# Connectors.net
KiCad netlist of a schematic drawn in Altium Designer
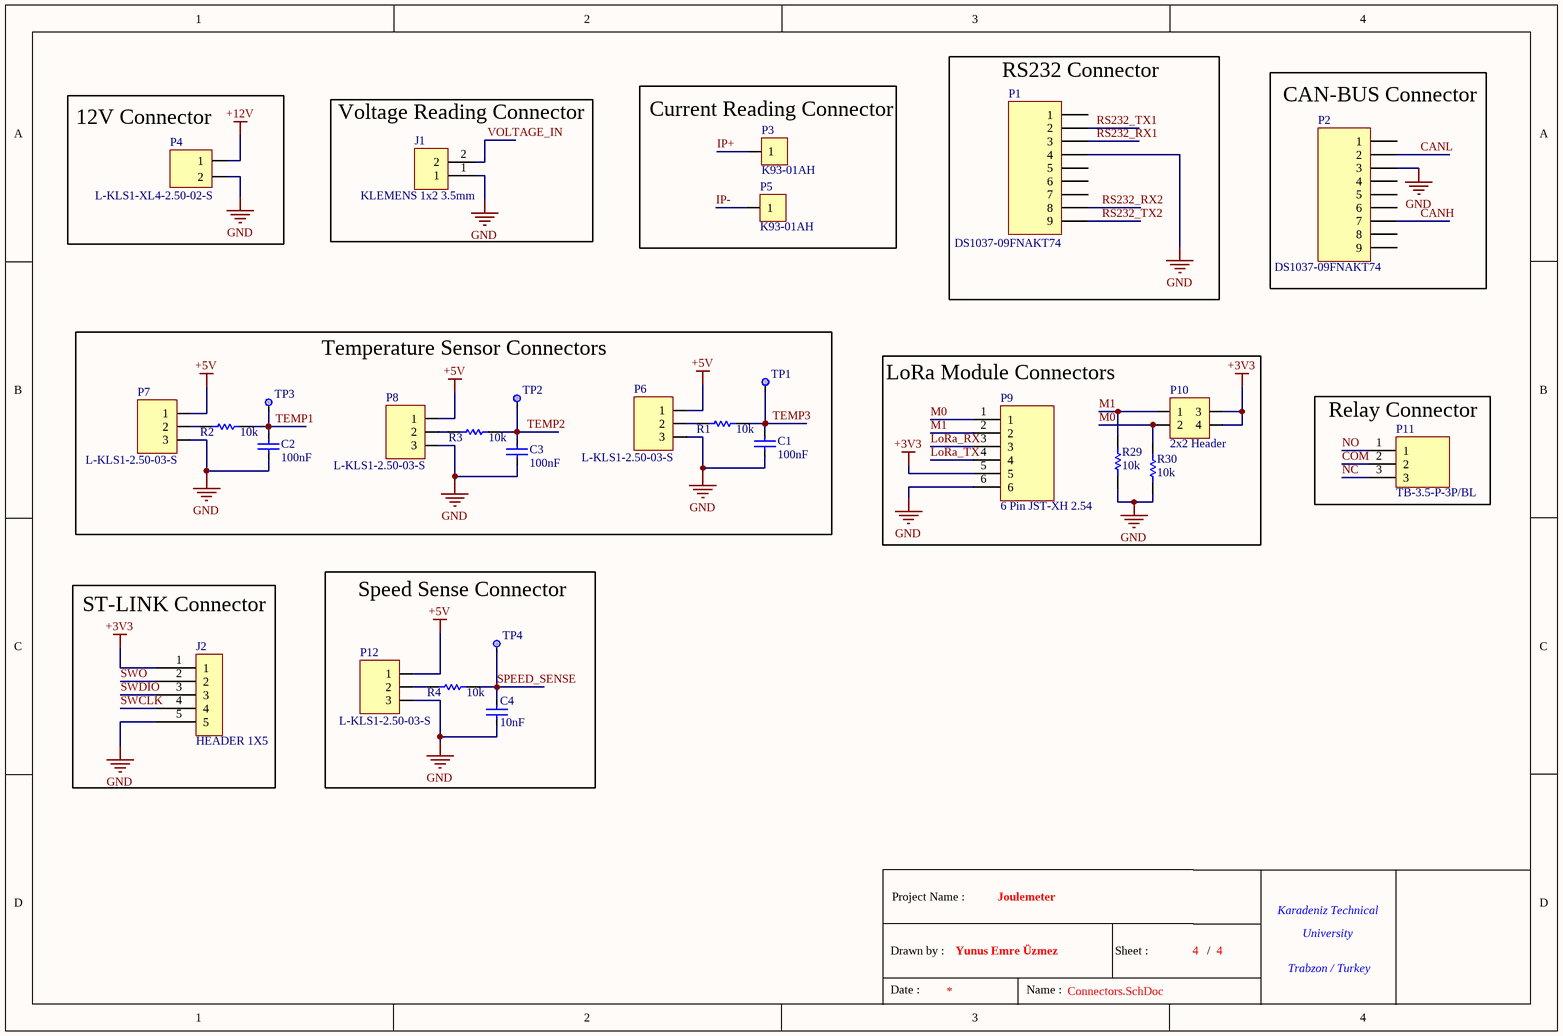
[diagram p0: Connectors.SchDoc]

(export (version "E")
  (design (tool "Eeschema 10.0.6"))
  (components
    (comp (ref "C1")
      (value "100nF")
      (footprint "CAP-0603")
      (fields
        (field (name "MANUFACTURER") "TDK")
        (field (name "VOLTAGE") "50V")
        (field (name "TOLERANCE") "%10")
      )
      (libsource (lib "My_Libs") (part "CGA3E2X7R1H104K080AA"))
    )
    (comp (ref "C2")
      (value "100nF")
      (footprint "Motor_Driver:CAP-0603")
      (fields
        (field (name "MANUFACTURER") "TDK")
        (field (name "VOLTAGE") "50V")
        (field (name "TOLERANCE") "%10")
      )
      (libsource (lib "My_Libs") (part "CGA3E2X7R1H104K080AA"))
    )
    (comp (ref "C3")
      (value "100nF")
      (footprint "Motor_Driver:CAP-0603")
      (fields
        (field (name "MANUFACTURER") "TDK")
        (field (name "VOLTAGE") "50V")
        (field (name "TOLERANCE") "%10")
      )
      (libsource (lib "My_Libs") (part "CGA3E2X7R1H104K080AA"))
    )
    (comp (ref "C4")
      (value "10nF")
      (footprint "CAP-0603")
      (fields
        (field (name "MANUFACTURER") "AVX")
        (field (name "VOLTAGE") "100V")
        (field (name "TOLERANCE") "%10")
      )
      (libsource (lib "Capacitor") (part "06031C103K4T4A"))
    )
    (comp (ref "J1")
      (value "KLEMENS 1x2 3.5mm")
      (footprint "Klemens 1X2 3.5mm")
      (description "1x2 3.5mm Klemens")
      (libsource (lib "model_satellite") (part "KLEMENS 1x2 3.5mm"))
    )
    (comp (ref "J2")
      (value "HEADER 1X5")
      (footprint "Header 2.54 1x5")
      (description "2.54mm 1x5 Header")
      (libsource (lib "model_satellite") (part "HEADER 1X5"))
    )
    (comp (ref "P1")
      (value "DS1037-09FNAKT74")
      (footprint "D SUB 9PIN FEMALE 90C TH")
      (fields (field (name "MANUFACTURER") "CONNFLY"))
      (libsource (lib "Motor_Driver") (part "DS1037-09FNAKT74"))
    )
    (comp (ref "P2")
      (value "DS1037-09FNAKT74")
      (footprint "D SUB 9PIN FEMALE 90C TH")
      (fields (field (name "MANUFACTURER") "CONNFLY"))
      (libsource (lib "Motor_Driver") (part "DS1037-09FNAKT74"))
    )
    (comp (ref "P3")
      (value "K93-01AH")
      (footprint "TERM.BLK.5.00MM BARRIER TYPE")
      (fields (field (name "MANUFACTURER") "GAOSONG"))
      (libsource (lib "Motor_Driver") (part "K93-01AH"))
    )
    (comp (ref "P4")
      (value "L-KLS1-XL4-2.50-02-S")
      (footprint "Motor_Driver_Module:2 PIN MALE 180C TH 2.50MM")
      (fields (field (name "MANUFACTURER") "KLS ELECTRONIC"))
      (libsource (lib "Motor_Driver_Module") (part "L-KLS1-XL4-2.50-02-S"))
    )
    (comp (ref "P5")
      (value "K93-01AH")
      (footprint "TERM.BLK.5.00MM BARRIER TYPE")
      (fields (field (name "MANUFACTURER") "GAOSONG"))
      (libsource (lib "Motor_Driver") (part "K93-01AH"))
    )
    (comp (ref "P6")
      (value "L-KLS1-2.50-03-S")
      (footprint "Motor_Driver:3PIN MALE 180C TH 2.5mm")
      (fields (field (name "MANUFACTURER") "KLS ELECTRONIC"))
      (libsource (lib "Motor_Driver_Module") (part "L-KLS1-2.50-03-S"))
    )
    (comp (ref "P7")
      (value "L-KLS1-2.50-03-S")
      (footprint "Motor_Driver:3PIN MALE 180C TH 2.5mm")
      (fields (field (name "MANUFACTURER") "KLS ELECTRONIC"))
      (libsource (lib "Motor_Driver_Module") (part "L-KLS1-2.50-03-S"))
    )
    (comp (ref "P8")
      (value "L-KLS1-2.50-03-S")
      (footprint "Motor_Driver:3PIN MALE 180C TH 2.5mm")
      (fields (field (name "MANUFACTURER") "KLS ELECTRONIC"))
      (libsource (lib "Motor_Driver_Module") (part "L-KLS1-2.50-03-S"))
    )
    (comp (ref "P9")
      (value "6 Pin JST-XH 2.54")
      (footprint "jl_lib:1x6 2.50mm TUNIC CONNECTOR")
      (fields (field (name "MANUFACTURER") "CONNFLY"))
      (libsource (lib "jl_lib") (part "6 Pin JST-XH 2.54"))
    )
    (comp (ref "P10")
      (value "2x2 Header")
      (footprint "2x2 Header (2.54mm)")
      (libsource (lib "Motor_Driver") (part "2x2 Header (2.54mm)"))
    )
    (comp (ref "P11")
      (value "TB-3.5-P-3P/BL")
      (footprint "1x3 3.50MM TERMINAL BLOCK")
      (fields (field (name "MANUFACTURER") "NINIGI"))
      (libsource (lib "jl_lib") (part "TB-3.5-P-3P/BL"))
    )
    (comp (ref "P12")
      (value "L-KLS1-2.50-03-S")
      (footprint "Motor_Driver:3PIN MALE 180C TH 2.5mm")
      (fields (field (name "MANUFACTURER") "KLS ELECTRONIC"))
      (libsource (lib "Motor_Driver_Module") (part "L-KLS1-2.50-03-S"))
    )
    (comp (ref "R1")
      (value "10k")
      (footprint "Motor_Driver:RES-0603")
      (fields
        (field (name "MANUFACTURER") "Vishay")
        (field (name "TOLERANCE") "%1")
        (field (name "POWER") "0.1W")
      )
      (libsource (lib "My_Libs") (part "CRCW060310K0FKEA"))
    )
    (comp (ref "R2")
      (value "10k")
      (footprint "Motor_Driver:RES-0603")
      (fields
        (field (name "MANUFACTURER") "Vishay")
        (field (name "TOLERANCE") "%1")
        (field (name "POWER") "0.1W")
      )
      (libsource (lib "My_Libs") (part "CRCW060310K0FKEA"))
    )
    (comp (ref "R3")
      (value "10k")
      (footprint "Motor_Driver:RES-0603")
      (fields
        (field (name "MANUFACTURER") "Vishay")
        (field (name "TOLERANCE") "%1")
        (field (name "POWER") "0.1W")
      )
      (libsource (lib "My_Libs") (part "CRCW060310K0FKEA"))
    )
    (comp (ref "R4")
      (value "10k")
      (footprint "Motor_Driver:RES-0603")
      (fields
        (field (name "MANUFACTURER") "Vishay")
        (field (name "TOLERANCE") "%1")
        (field (name "POWER") "0.1W")
      )
      (libsource (lib "My_Libs") (part "CRCW060310K0FKEA"))
    )
    (comp (ref "R29")
      (value "10k")
      (footprint "RES-0603")
      (fields
        (field (name "MANUFACTURER") "Vishay")
        (field (name "TOLERANCE") "%1")
        (field (name "POWER") "0.1W")
      )
      (libsource (lib "Motor_Driver") (part "CRCW060310K0FKEA"))
    )
    (comp (ref "R30")
      (value "10k")
      (footprint "RES-0603")
      (fields
        (field (name "MANUFACTURER") "Vishay")
        (field (name "TOLERANCE") "%1")
        (field (name "POWER") "0.1W")
      )
      (libsource (lib "Motor_Driver") (part "CRCW060310K0FKEA"))
    )
    (comp (ref "TP1")
      (value "Test Point")
      (footprint "0.8mm Test Point")
      (libsource (lib "Motor_Driver") (part "Test Point"))
    )
    (comp (ref "TP2")
      (value "Test Point")
      (footprint "0.8mm Test Point")
      (libsource (lib "Motor_Driver") (part "Test Point"))
    )
    (comp (ref "TP3")
      (value "Test Point")
      (footprint "0.8mm Test Point")
      (libsource (lib "Motor_Driver") (part "Test Point"))
    )
    (comp (ref "TP4")
      (value "Test Point")
      (footprint "0.8mm Test Point")
      (libsource (lib "Motor_Driver") (part "Test Point"))
    )
  )
  (nets
    (net (code "1") (name "+3V3") (class "Default")
      (node (ref "J2") (pin "1") (pinfunction "1_1") (pintype "passive"))
      (node (ref "P10") (pin "3") (pinfunction "3_3") (pintype "passive"))
      (node (ref "P10") (pin "4") (pinfunction "4_4") (pintype "passive"))
      (node (ref "P9") (pin "5") (pinfunction "5_5") (pintype "passive"))
    )
    (net (code "2") (name "+5V") (class "Default")
      (node (ref "P12") (pin "1") (pinfunction "1_1") (pintype "passive"))
      (node (ref "P6") (pin "1") (pinfunction "1_1") (pintype "passive"))
      (node (ref "P7") (pin "1") (pinfunction "1_1") (pintype "passive"))
      (node (ref "P8") (pin "1") (pinfunction "1_1") (pintype "passive"))
    )
    (net (code "3") (name "+12V") (class "Default")
      (node (ref "P4") (pin "1") (pinfunction "1_1") (pintype "passive"))
    )
    (net (code "4") (name "/CANH") (class "Default")
      (node (ref "P2") (pin "7") (pinfunction "7_7") (pintype "passive"))
    )
    (net (code "5") (name "/CANL") (class "Default")
      (node (ref "P2") (pin "2") (pinfunction "2_2") (pintype "passive"))
    )
    (net (code "6") (name "/COM") (class "Default")
      (node (ref "P11") (pin "2") (pinfunction "2_2") (pintype "passive"))
    )
    (net (code "7") (name "/IP+") (class "Default")
      (node (ref "P3") (pin "1") (pinfunction "1_1") (pintype "passive"))
    )
    (net (code "8") (name "/IP-") (class "Default")
      (node (ref "P5") (pin "1") (pinfunction "1_1") (pintype "passive"))
    )
    (net (code "9") (name "/LoRa_RX") (class "Default")
      (node (ref "P9") (pin "3") (pinfunction "3_3") (pintype "passive"))
    )
    (net (code "10") (name "/LoRa_TX") (class "Default")
      (node (ref "P9") (pin "4") (pinfunction "4_4") (pintype "passive"))
    )
    (net (code "11") (name "/M0") (class "Default")
      (node (ref "P10") (pin "2") (pinfunction "2_2") (pintype "passive"))
      (node (ref "P9") (pin "1") (pinfunction "1_1") (pintype "passive"))
      (node (ref "R30") (pin "2") (pinfunction "2_2") (pintype "passive"))
    )
    (net (code "12") (name "/M1") (class "Default")
      (node (ref "P10") (pin "1") (pinfunction "1_1") (pintype "passive"))
      (node (ref "P9") (pin "2") (pinfunction "2_2") (pintype "passive"))
      (node (ref "R29") (pin "2") (pinfunction "2_2") (pintype "passive"))
    )
    (net (code "13") (name "/NC") (class "Default")
      (node (ref "P11") (pin "3") (pinfunction "3_3") (pintype "passive"))
    )
    (net (code "14") (name "/NO") (class "Default")
      (node (ref "P11") (pin "1") (pinfunction "1_1") (pintype "passive"))
    )
    (net (code "15") (name "/RS232_RX1") (class "Default")
      (node (ref "P1") (pin "3") (pinfunction "3_3") (pintype "passive"))
    )
    (net (code "16") (name "/RS232_RX2") (class "Default")
      (node (ref "P1") (pin "8") (pinfunction "8_8") (pintype "passive"))
    )
    (net (code "17") (name "/RS232_TX1") (class "Default")
      (node (ref "P1") (pin "2") (pinfunction "2_2") (pintype "passive"))
    )
    (net (code "18") (name "/RS232_TX2") (class "Default")
      (node (ref "P1") (pin "9") (pinfunction "9_9") (pintype "passive"))
    )
    (net (code "19") (name "/SPEED_SENSE") (class "Default")
      (node (ref "C4") (pin "2") (pinfunction "2_2") (pintype "passive"))
      (node (ref "R4") (pin "1") (pinfunction "1_1") (pintype "passive"))
      (node (ref "TP4") (pin "1") (pinfunction "1_1") (pintype "passive"))
    )
    (net (code "20") (name "/SWCLK") (class "Default")
      (node (ref "J2") (pin "4") (pinfunction "4_4") (pintype "passive"))
    )
    (net (code "21") (name "/SWDIO") (class "Default")
      (node (ref "J2") (pin "3") (pinfunction "3_3") (pintype "passive"))
    )
    (net (code "22") (name "/SWO") (class "Default")
      (node (ref "J2") (pin "2") (pinfunction "2_2") (pintype "passive"))
    )
    (net (code "23") (name "/TEMP1") (class "Default")
      (node (ref "C2") (pin "2") (pinfunction "2_2") (pintype "passive"))
      (node (ref "R2") (pin "1") (pinfunction "1_1") (pintype "passive"))
      (node (ref "TP3") (pin "1") (pinfunction "1_1") (pintype "passive"))
    )
    (net (code "24") (name "/TEMP2") (class "Default")
      (node (ref "C3") (pin "2") (pinfunction "2_2") (pintype "passive"))
      (node (ref "R3") (pin "1") (pinfunction "1_1") (pintype "passive"))
      (node (ref "TP2") (pin "1") (pinfunction "1_1") (pintype "passive"))
    )
    (net (code "25") (name "/TEMP3") (class "Default")
      (node (ref "C1") (pin "2") (pinfunction "2_2") (pintype "passive"))
      (node (ref "R1") (pin "1") (pinfunction "1_1") (pintype "passive"))
      (node (ref "TP1") (pin "1") (pinfunction "1_1") (pintype "passive"))
    )
    (net (code "26") (name "/VOLTAGE_IN") (class "Default")
      (node (ref "J1") (pin "2") (pinfunction "2_2") (pintype "passive"))
    )
    (net (code "27") (name "GND") (class "Default")
      (node (ref "C1") (pin "1") (pinfunction "1_1") (pintype "passive"))
      (node (ref "C2") (pin "1") (pinfunction "1_1") (pintype "passive"))
      (node (ref "C3") (pin "1") (pinfunction "1_1") (pintype "passive"))
      (node (ref "C4") (pin "1") (pinfunction "1_1") (pintype "passive"))
      (node (ref "J1") (pin "1") (pinfunction "1_1") (pintype "passive"))
      (node (ref "J2") (pin "5") (pinfunction "5_5") (pintype "passive"))
      (node (ref "P1") (pin "4") (pinfunction "4_4") (pintype "passive"))
      (node (ref "P12") (pin "3") (pinfunction "3_3") (pintype "passive"))
      (node (ref "P2") (pin "3") (pinfunction "3_3") (pintype "passive"))
      (node (ref "P4") (pin "2") (pinfunction "2_2") (pintype "passive"))
      (node (ref "P6") (pin "3") (pinfunction "3_3") (pintype "passive"))
      (node (ref "P7") (pin "3") (pinfunction "3_3") (pintype "passive"))
      (node (ref "P8") (pin "3") (pinfunction "3_3") (pintype "passive"))
      (node (ref "P9") (pin "6") (pinfunction "6_6") (pintype "passive"))
      (node (ref "R29") (pin "1") (pinfunction "1_1") (pintype "passive"))
      (node (ref "R30") (pin "1") (pinfunction "1_1") (pintype "passive"))
    )
    (net (code "28") (name "Net-(P6-Pad2)") (class "Default")
      (node (ref "P6") (pin "2") (pinfunction "2_2") (pintype "passive"))
      (node (ref "R1") (pin "2") (pinfunction "2_2") (pintype "passive"))
    )
    (net (code "29") (name "Net-(P7-Pad2)") (class "Default")
      (node (ref "P7") (pin "2") (pinfunction "2_2") (pintype "passive"))
      (node (ref "R2") (pin "2") (pinfunction "2_2") (pintype "passive"))
    )
    (net (code "30") (name "Net-(P8-Pad2)") (class "Default")
      (node (ref "P8") (pin "2") (pinfunction "2_2") (pintype "passive"))
      (node (ref "R3") (pin "2") (pinfunction "2_2") (pintype "passive"))
    )
    (net (code "31") (name "Net-(P12-Pad2)") (class "Default")
      (node (ref "P12") (pin "2") (pinfunction "2_2") (pintype "passive"))
      (node (ref "R4") (pin "2") (pinfunction "2_2") (pintype "passive"))
    )
    (net (code "32") (name "unconnected-(P1-Pad1)") (class "Default")
      (node (ref "P1") (pin "1") (pinfunction "1_1") (pintype "passive"))
    )
    (net (code "33") (name "unconnected-(P1-Pad5)") (class "Default")
      (node (ref "P1") (pin "5") (pinfunction "5_5") (pintype "passive"))
    )
    (net (code "34") (name "unconnected-(P1-Pad6)") (class "Default")
      (node (ref "P1") (pin "6") (pinfunction "6_6") (pintype "passive"))
    )
    (net (code "35") (name "unconnected-(P1-Pad7)") (class "Default")
      (node (ref "P1") (pin "7") (pinfunction "7_7") (pintype "passive"))
    )
    (net (code "36") (name "unconnected-(P2-Pad1)") (class "Default")
      (node (ref "P2") (pin "1") (pinfunction "1_1") (pintype "passive"))
    )
    (net (code "37") (name "unconnected-(P2-Pad4)") (class "Default")
      (node (ref "P2") (pin "4") (pinfunction "4_4") (pintype "passive"))
    )
    (net (code "38") (name "unconnected-(P2-Pad5)") (class "Default")
      (node (ref "P2") (pin "5") (pinfunction "5_5") (pintype "passive"))
    )
    (net (code "39") (name "unconnected-(P2-Pad6)") (class "Default")
      (node (ref "P2") (pin "6") (pinfunction "6_6") (pintype "passive"))
    )
    (net (code "40") (name "unconnected-(P2-Pad8)") (class "Default")
      (node (ref "P2") (pin "8") (pinfunction "8_8") (pintype "passive"))
    )
    (net (code "41") (name "unconnected-(P2-Pad9)") (class "Default")
      (node (ref "P2") (pin "9") (pinfunction "9_9") (pintype "passive"))
    )
  )
)
